# IMU.net
KiCad netlist of a schematic drawn in Altium Designer
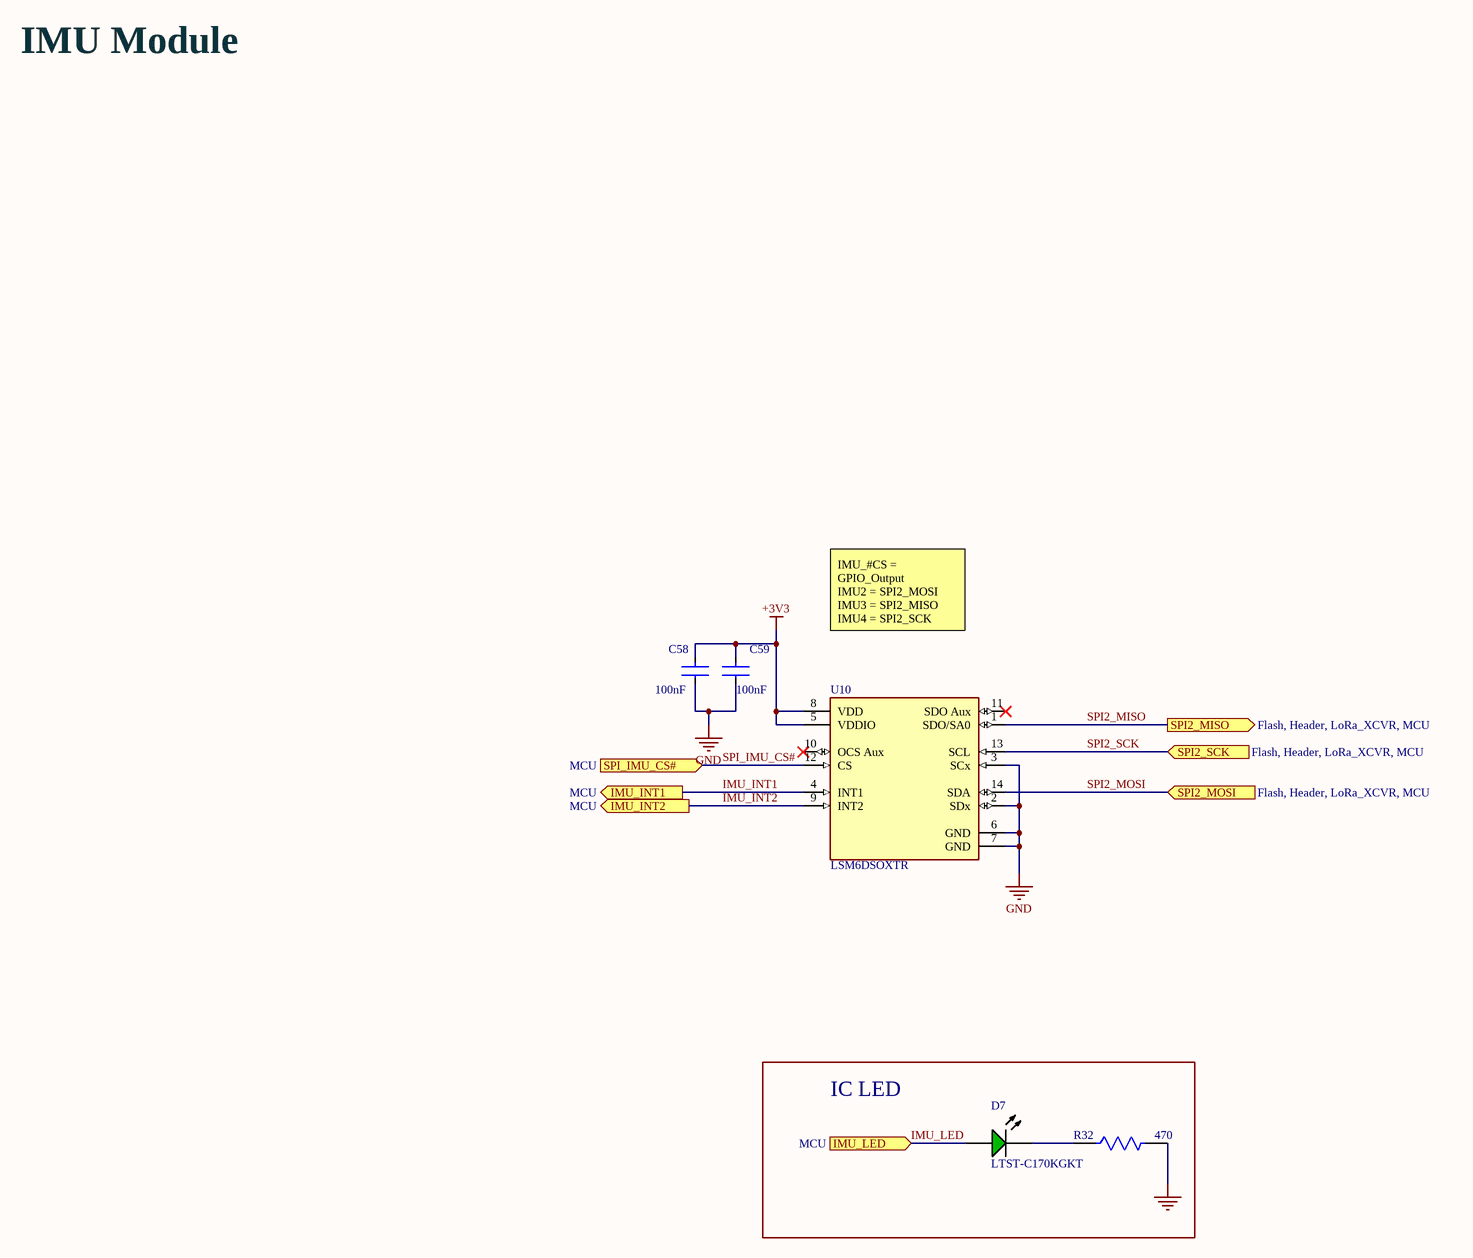
[diagram p0: IMU.SchDoc]

(export (version "E")
  (design (tool "Eeschema 10.0.6"))
  (components
    (comp (ref "C58")
      (value "100nF")
      (footprint "FP-GRM15-MFG")
      (description "CAP CER 0.1UF 16V X7R 0402")
      (fields (field (name "MANUFACTURER PART NUMBER") "GRM155R71C104KA88D") (field (name "TOLERANCE") "10%"))
      (libsource (lib "Altium Content Vault") (part "236180d848d6139a670b325ea6854c9"))
    )
    (comp (ref "C59")
      (value "100nF")
      (footprint "FP-GRM15-MFG")
      (description "CAP CER 0.1UF 16V X7R 0402")
      (fields (field (name "MANUFACTURER PART NUMBER") "GRM155R71C104KA88D") (field (name "TOLERANCE") "10%"))
      (libsource (lib "Altium Content Vault") (part "236180d848d6139a670b325ea6854c9"))
    )
    (comp (ref "D7")
      (value "LTST-C170KGKT")
      (footprint "LTST-LTST-C170KGKT-2_V")
      (description "Ultra Bright AlInGaP Chip LED, 75 mW, -55 to 85 degC, 2-Pin SMD (0805), RoHS, Tape and Reel")
      (fields (field (name "MANUFACTURER") "Lite-On"))
      (libsource (lib "Altium Content Vault") (part "LED-GREEN-KA-2"))
    )
    (comp (ref "R32")
      (value "470")
      (footprint "FP-CPF0603-MFG")
      (description "RES SMD 470Ω 0.1% 1/16W 0603\r\n\r\nCPF0603B470RE")
      (fields
        (field (name "MANUFACTURER") "TE Connectivity")
        (field (name "MANUFACTURER PART NUMBER") "CPF0603B470RE")
      )
      (libsource (lib "Altium Content Vault") (part "1029c3af85768c4190bb7ad29bc67b5"))
    )
    (comp (ref "U10")
      (value "LSM6DSOXTR")
      (footprint "FP-LGA-14L-DM00249496-MFG")
      (description "INEMO INERTIAL MODULE: 3D ACCELE")
      (fields
        (field (name "OCTOPART") "https://octopart.com/lsm6dsoxtr-stmicroelectronics-98102600")
        (field (name "MANUFACTURER") "STMicroelectronics")
      )
      (libsource (lib "Altium Content Vault") (part "e907d670a73553dd54601dfd5d274f3"))
    )
  )
  (nets
    (net (code "1") (name "+3V3") (class "Default")
      (node (ref "C58") (pin "2") (pinfunction "2_2") (pintype "passive"))
      (node (ref "C59") (pin "2") (pinfunction "2_2") (pintype "passive"))
      (node (ref "U10") (pin "5") (pinfunction "VDDIO_5") (pintype "power_in"))
      (node (ref "U10") (pin "8") (pinfunction "VDD_8") (pintype "power_in"))
    )
    (net (code "3") (name "/IMU_INT1") (class "Default")
      (node (ref "U10") (pin "4") (pinfunction "INT1_4") (pintype "input"))
    )
    (net (code "4") (name "/IMU_INT2") (class "Default")
      (node (ref "U10") (pin "9") (pinfunction "INT2_9") (pintype "input"))
    )
    (net (code "5") (name "/IMU_LED") (class "Default")
      (node (ref "D7") (pin "2") (pinfunction "A_2") (pintype "passive"))
    )
    (net (code "6") (name "/SPI2_MISO") (class "Default")
      (node (ref "U10") (pin "1") (pinfunction "SDO/SA0_1") (pintype "bidirectional"))
    )
    (net (code "7") (name "/SPI2_MOSI") (class "Default")
      (node (ref "U10") (pin "14") (pinfunction "SDA_14") (pintype "bidirectional"))
    )
    (net (code "8") (name "/SPI2_SCK") (class "Default")
      (node (ref "U10") (pin "13") (pinfunction "SCL_13") (pintype "input"))
    )
    (net (code "9") (name "/SPI_IMU_CS#") (class "Default")
      (node (ref "U10") (pin "12") (pinfunction "CS_12") (pintype "input"))
    )
    (net (code "10") (name "GND") (class "Default")
      (node (ref "C58") (pin "1") (pinfunction "1_1") (pintype "passive"))
      (node (ref "C59") (pin "1") (pinfunction "1_1") (pintype "passive"))
      (node (ref "R32") (pin "2") (pinfunction "2_2") (pintype "passive"))
      (node (ref "U10") (pin "2") (pinfunction "SDx_2") (pintype "bidirectional"))
      (node (ref "U10") (pin "3") (pinfunction "SCx_3") (pintype "input"))
      (node (ref "U10") (pin "6") (pinfunction "GND_6") (pintype "power_in"))
      (node (ref "U10") (pin "7") (pinfunction "GND_7") (pintype "power_in"))
    )
    (net (code "11") (name "Net-(D7-K)") (class "Default")
      (node (ref "D7") (pin "1") (pinfunction "K_1") (pintype "passive"))
      (node (ref "R32") (pin "1") (pinfunction "1_1") (pintype "passive"))
    )
    (net (code "12") (name "unconnected-(U10-OCS_Aux-Pad10)") (class "Default")
      (node (ref "U10") (pin "10") (pinfunction "OCS_Aux_10") (pintype "bidirectional+no_connect"))
    )
    (net (code "13") (name "unconnected-(U10-SDO_Aux-Pad11)") (class "Default")
      (node (ref "U10") (pin "11") (pinfunction "SDO_Aux_11") (pintype "bidirectional+no_connect"))
    )
  )
)
